# mboard_mcu_2.net
KiCad netlist of a schematic drawn in Altium Designer
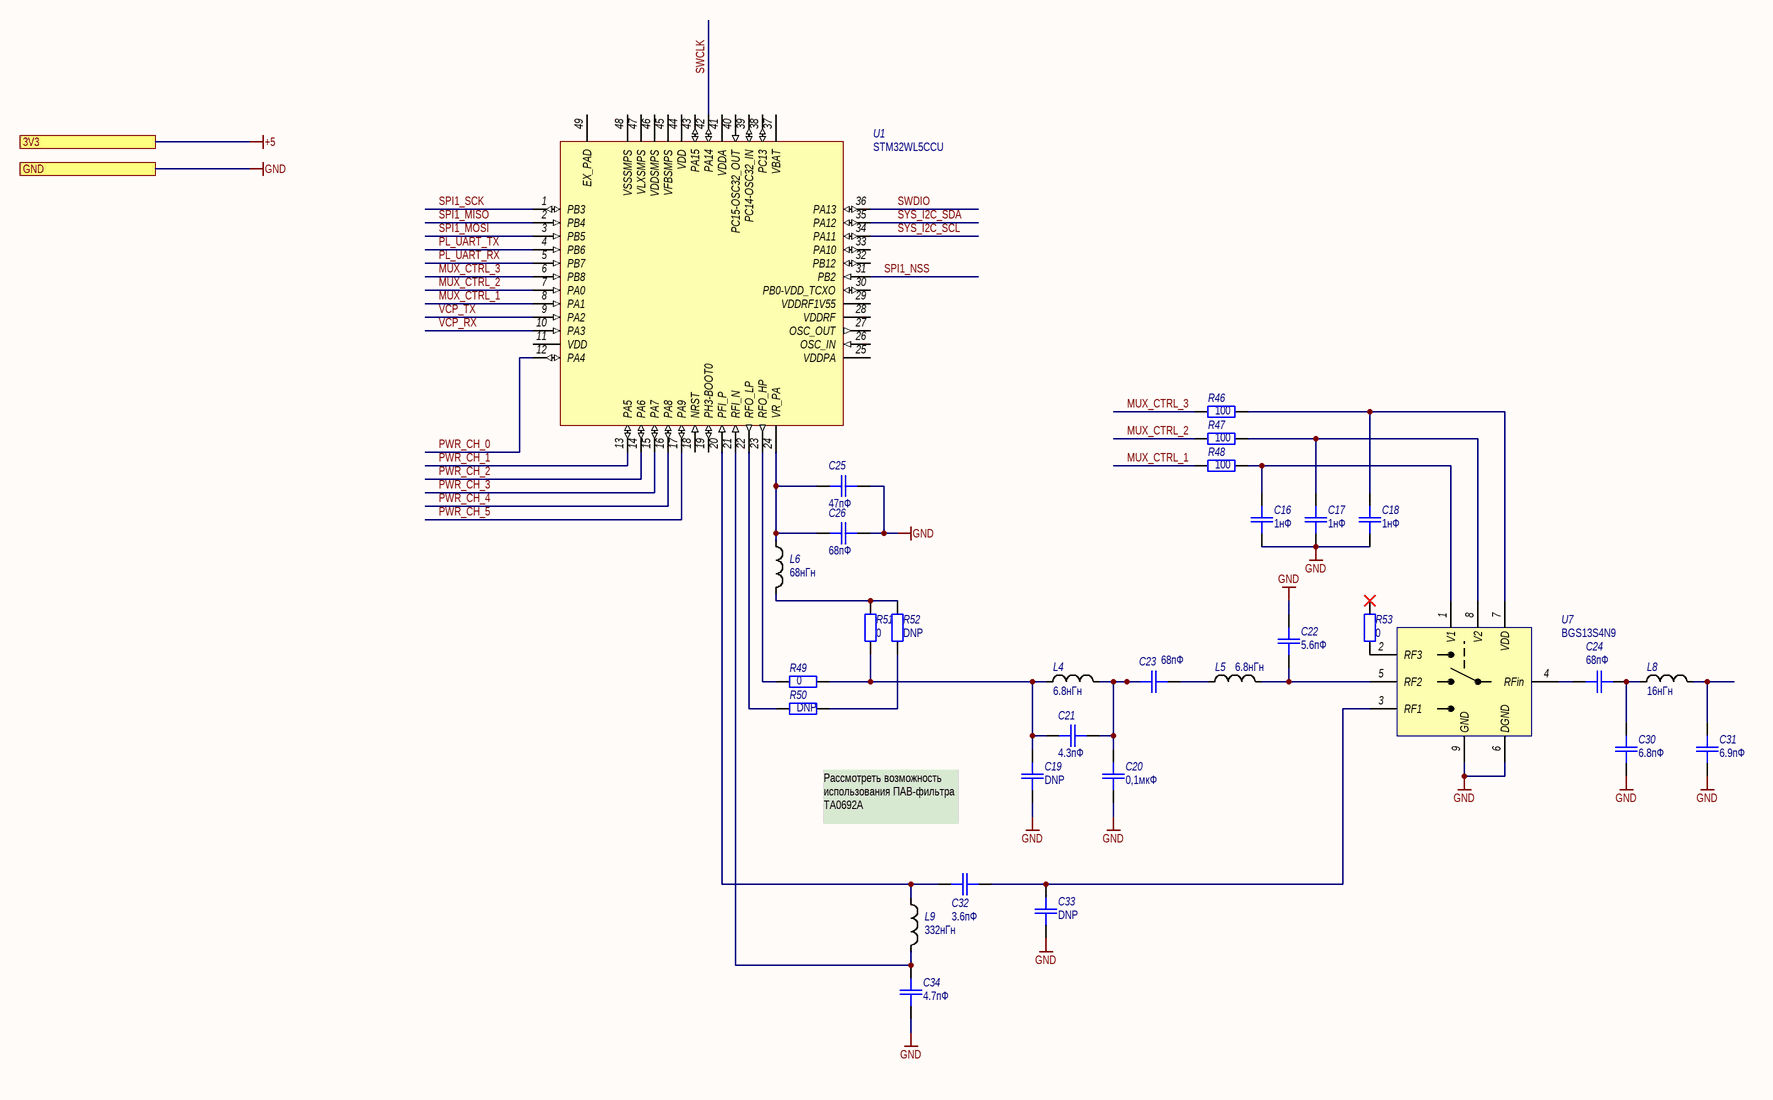
[diagram p0: mboard_mcu (2).SchDoc]

(export (version "E")
  (design (tool "Eeschema 10.0.6"))
  (components
    (comp (ref "C16")
      (value "1нФ")
      (footprint "SMD_C0402")
      (description "Capacitor")
      (fields (field (name "Comment") "K10-79"))
      (libsource (lib "Passive") (part "Capacitor"))
    )
    (comp (ref "C17")
      (value "1нФ")
      (footprint "SMD_C0402")
      (description "Capacitor")
      (fields (field (name "Comment") "K10-79"))
      (libsource (lib "Passive") (part "Capacitor"))
    )
    (comp (ref "C18")
      (value "1нФ")
      (footprint "SMD_C0402")
      (description "Capacitor")
      (fields (field (name "Comment") "K10-79"))
      (libsource (lib "Passive") (part "Capacitor"))
    )
    (comp (ref "C19")
      (value "DNP")
      (footprint "SMD_C0402")
      (description "Capacitor")
      (fields (field (name "Comment") "K10-79"))
      (libsource (lib "Passive") (part "Capacitor"))
    )
    (comp (ref "C20")
      (value "0,1мкФ")
      (footprint "SMD_C0402")
      (description "Capacitor")
      (fields (field (name "Comment") "K10-79"))
      (libsource (lib "Passive") (part "Capacitor"))
    )
    (comp (ref "C21")
      (value "4.3пФ")
      (footprint "SMD_C0402")
      (description "Capacitor")
      (fields (field (name "Comment") "K10-79"))
      (libsource (lib "Passive") (part "Capacitor"))
    )
    (comp (ref "C22")
      (value "5.6пФ")
      (footprint "SMD_C0402")
      (description "Capacitor")
      (fields (field (name "Comment") "K10-79"))
      (libsource (lib "Passive") (part "Capacitor"))
    )
    (comp (ref "C23")
      (value "68пФ")
      (footprint "SMD_C0603")
      (description "Capacitor")
      (fields (field (name "Comment") "K10-79"))
      (libsource (lib "Passive") (part "Capacitor"))
    )
    (comp (ref "C24")
      (value "68пФ")
      (footprint "SMD_C0402")
      (description "Capacitor")
      (fields (field (name "Comment") "K10-79"))
      (libsource (lib "Passive") (part "Capacitor"))
    )
    (comp (ref "C25")
      (value "47пФ")
      (footprint "SMD_C0402")
      (description "Capacitor")
      (fields (field (name "Comment") "K10-79"))
      (libsource (lib "Passive") (part "Capacitor"))
    )
    (comp (ref "C26")
      (value "68пФ")
      (footprint "SMD_C0402")
      (description "Capacitor")
      (fields (field (name "Comment") "K10-79"))
      (libsource (lib "Passive") (part "Capacitor"))
    )
    (comp (ref "C30")
      (value "6.8пФ")
      (footprint "SMD_C0402")
      (description "Capacitor")
      (fields (field (name "Comment") "K10-79"))
      (libsource (lib "Passive") (part "Capacitor"))
    )
    (comp (ref "C31")
      (value "6.9пФ")
      (footprint "SMD_C0402")
      (description "Capacitor")
      (fields (field (name "Comment") "K10-79"))
      (libsource (lib "Passive") (part "Capacitor"))
    )
    (comp (ref "C32")
      (value "3.6пФ")
      (footprint "SMD_C0603")
      (description "Capacitor")
      (fields (field (name "Comment") "K10-79"))
      (libsource (lib "Passive") (part "Capacitor"))
    )
    (comp (ref "C33")
      (value "DNP")
      (footprint "SMD_C0603")
      (description "Capacitor")
      (fields (field (name "Comment") "K10-79"))
      (libsource (lib "Passive") (part "Capacitor"))
    )
    (comp (ref "C34")
      (value "4.7пФ")
      (footprint "SMD_C0603")
      (description "Capacitor")
      (fields (field (name "Comment") "K10-79"))
      (libsource (lib "Passive") (part "Capacitor"))
    )
    (comp (ref "L4")
      (value "6.8нГн")
      (footprint "SMD_0805")
      (description "Inductor")
      (libsource (lib "") (part "Inductor_1"))
    )
    (comp (ref "L5")
      (value "6.8нГн")
      (footprint "SMD_0805")
      (description "Inductor")
      (libsource (lib "Passive") (part "Inductor"))
    )
    (comp (ref "L6")
      (value "68нГн")
      (footprint "SMD_0805")
      (description "Inductor")
      (libsource (lib "Passive") (part "Inductor"))
    )
    (comp (ref "L8")
      (value "16нГн")
      (footprint "SMD_0805")
      (description "Inductor")
      (libsource (lib "Passive") (part "Inductor"))
    )
    (comp (ref "L9")
      (value "332нГн")
      (footprint "SMD_0805")
      (description "Inductor")
      (libsource (lib "Passive") (part "Inductor"))
    )
    (comp (ref "R46")
      (value "100")
      (footprint "SMD_0805")
      (description "Resistor")
      (fields (field (name "Comment") "OSM R1-12"))
      (libsource (lib "") (part "Resistor_1"))
    )
    (comp (ref "R47")
      (value "100")
      (footprint "SMD_0805")
      (description "Resistor")
      (fields (field (name "Comment") "OSM R1-12"))
      (libsource (lib "") (part "Resistor_1"))
    )
    (comp (ref "R48")
      (value "100")
      (footprint "SMD_0805")
      (description "Resistor")
      (fields (field (name "Comment") "OSM R1-12"))
      (libsource (lib "") (part "Resistor_1"))
    )
    (comp (ref "R49")
      (value "0")
      (footprint "SMD_0805")
      (description "Resistor")
      (fields (field (name "Comment") "OSM R1-12"))
      (libsource (lib "") (part "Resistor_1"))
    )
    (comp (ref "R50")
      (value "DNP")
      (footprint "SMD_0805")
      (description "Resistor")
      (fields (field (name "Comment") "OSM R1-12"))
      (libsource (lib "") (part "Resistor_1"))
    )
    (comp (ref "R51")
      (value "0")
      (footprint "SMD_0805")
      (description "Resistor")
      (fields (field (name "Comment") "OSM R1-12"))
      (libsource (lib "") (part "Resistor_2"))
    )
    (comp (ref "R52")
      (value "DNP")
      (footprint "SMD_0805")
      (description "Resistor")
      (fields (field (name "Comment") "OSM R1-12"))
      (libsource (lib "") (part "Resistor_2"))
    )
    (comp (ref "R53")
      (value "0")
      (footprint "SMD_0805")
      (description "Resistor")
      (fields (field (name "Comment") "OSM R1-12"))
      (libsource (lib "Passive") (part "Resistor"))
    )
    (comp (ref "U1")
      (value "STM32WL5CCU")
      (footprint "UQFNPN48")
      (description "Multiprotocol Wireless 32-bit MCU with LPWAN Sub-GHz radio solution")
      (fields (field (name "НАИМЕНОВАНИЕ") "STM32WL5CCU"))
      (libsource (lib "MCU") (part "STM32WL5CCU"))
    )
    (comp (ref "U7")
      (value "BGS13S4N9")
      (footprint "TSNP-9-3")
      (description "Wideband RF SP3T Switch")
      (fields
        (field (name "INTERNAL_PART_NUMBER") "MCD-02018")
        (field (name "MANUFACTURER") "INFINEON")
        (field (name "НАИМЕНОВАНИЕ") "BGS13S4N9")
        (field (name "PROVIDED_BY") "SUBCO")
      )
      (libsource (lib "RF") (part "BGS13S4N9"))
    )
  )
  (nets
    (net (code "2") (name "/MUX_CTRL_1") (class "Default")
      (node (ref "R48") (pin "1") (pinfunction "1_1") (pintype "passive"))
      (node (ref "U1") (pin "8") (pinfunction "PA1_8") (pintype "input"))
    )
    (net (code "3") (name "/MUX_CTRL_2") (class "Default")
      (node (ref "R47") (pin "1") (pinfunction "1_1") (pintype "passive"))
      (node (ref "U1") (pin "7") (pinfunction "PA0_7") (pintype "input"))
    )
    (net (code "4") (name "/MUX_CTRL_3") (class "Default")
      (node (ref "R46") (pin "1") (pinfunction "1_1") (pintype "passive"))
      (node (ref "U1") (pin "6") (pinfunction "PB8_6") (pintype "input"))
    )
    (net (code "5") (name "/PL_UART_RX") (class "Default")
      (node (ref "U1") (pin "5") (pinfunction "PB7_5") (pintype "input"))
    )
    (net (code "6") (name "/PL_UART_TX") (class "Default")
      (node (ref "U1") (pin "4") (pinfunction "PB6_4") (pintype "input"))
    )
    (net (code "7") (name "/PWR_CH_0") (class "Default")
      (node (ref "U1") (pin "12") (pinfunction "PA4_12") (pintype "bidirectional"))
    )
    (net (code "8") (name "/PWR_CH_1") (class "Default")
      (node (ref "U1") (pin "13") (pinfunction "PA5_13") (pintype "bidirectional"))
    )
    (net (code "9") (name "/PWR_CH_2") (class "Default")
      (node (ref "U1") (pin "14") (pinfunction "PA6_14") (pintype "bidirectional"))
    )
    (net (code "10") (name "/PWR_CH_3") (class "Default")
      (node (ref "U1") (pin "15") (pinfunction "PA7_15") (pintype "bidirectional"))
    )
    (net (code "11") (name "/PWR_CH_4") (class "Default")
      (node (ref "U1") (pin "16") (pinfunction "PA8_16") (pintype "bidirectional"))
    )
    (net (code "12") (name "/PWR_CH_5") (class "Default")
      (node (ref "U1") (pin "17") (pinfunction "PA9_17") (pintype "bidirectional"))
    )
    (net (code "13") (name "/SPI1_MISO") (class "Default")
      (node (ref "U1") (pin "2") (pinfunction "PB4_2") (pintype "input"))
    )
    (net (code "14") (name "/SPI1_MOSI") (class "Default")
      (node (ref "U1") (pin "3") (pinfunction "PB5_3") (pintype "input"))
    )
    (net (code "15") (name "/SPI1_NSS") (class "Default")
      (node (ref "U1") (pin "31") (pinfunction "PB2_31") (pintype "input"))
    )
    (net (code "16") (name "/SPI1_SCK") (class "Default")
      (node (ref "U1") (pin "1") (pinfunction "PB3_1") (pintype "bidirectional"))
    )
    (net (code "17") (name "/SWCLK") (class "Default")
      (node (ref "U1") (pin "42") (pinfunction "PA14_42") (pintype "bidirectional"))
    )
    (net (code "18") (name "/SWDIO") (class "Default")
      (node (ref "U1") (pin "36") (pinfunction "PA13_36") (pintype "bidirectional"))
    )
    (net (code "19") (name "/SYS_I2C_SCL") (class "Default")
      (node (ref "U1") (pin "34") (pinfunction "PA11_34") (pintype "bidirectional"))
    )
    (net (code "20") (name "/SYS_I2C_SDA") (class "Default")
      (node (ref "U1") (pin "35") (pinfunction "PA12_35") (pintype "bidirectional"))
    )
    (net (code "21") (name "/VCP_RX") (class "Default")
      (node (ref "U1") (pin "10") (pinfunction "PA3_10") (pintype "input"))
    )
    (net (code "22") (name "/VCP_TX") (class "Default")
      (node (ref "U1") (pin "9") (pinfunction "PA2_9") (pintype "input"))
    )
    (net (code "23") (name "GND") (class "Default")
      (node (ref "C16") (pin "1") (pinfunction "1_1") (pintype "passive"))
      (node (ref "C17") (pin "1") (pinfunction "1_1") (pintype "passive"))
      (node (ref "C18") (pin "1") (pinfunction "1_1") (pintype "passive"))
      (node (ref "C19") (pin "2") (pinfunction "2_2") (pintype "passive"))
      (node (ref "C20") (pin "2") (pinfunction "2_2") (pintype "passive"))
      (node (ref "C22") (pin "2") (pinfunction "2_2") (pintype "passive"))
      (node (ref "C25") (pin "2") (pinfunction "2_2") (pintype "passive"))
      (node (ref "C26") (pin "2") (pinfunction "2_2") (pintype "passive"))
      (node (ref "C30") (pin "1") (pinfunction "1_1") (pintype "passive"))
      (node (ref "C31") (pin "1") (pinfunction "1_1") (pintype "passive"))
      (node (ref "C33") (pin "1") (pinfunction "1_1") (pintype "passive"))
      (node (ref "C34") (pin "2") (pinfunction "2_2") (pintype "passive"))
      (node (ref "U7") (pin "6") (pinfunction "DGND_6") (pintype "passive"))
      (node (ref "U7") (pin "9") (pinfunction "GND_9") (pintype "passive"))
    )
    (net (code "24") (name "Net-(C19-Pad1)") (class "Default")
      (node (ref "C19") (pin "1") (pinfunction "1_1") (pintype "passive"))
      (node (ref "C21") (pin "1") (pinfunction "1_1") (pintype "passive"))
      (node (ref "L4") (pin "2") (pinfunction "2_2") (pintype "passive"))
      (node (ref "R49") (pin "2") (pinfunction "2_2") (pintype "passive"))
      (node (ref "R51") (pin "1") (pinfunction "1_1") (pintype "passive"))
    )
    (net (code "25") (name "Net-(C20-Pad1)") (class "Default")
      (node (ref "C20") (pin "1") (pinfunction "1_1") (pintype "passive"))
      (node (ref "C21") (pin "2") (pinfunction "2_2") (pintype "passive"))
      (node (ref "C23") (pin "1") (pinfunction "1_1") (pintype "passive"))
      (node (ref "L4") (pin "1") (pinfunction "1_1") (pintype "passive"))
    )
    (net (code "26") (name "Net-(C23-Pad2)") (class "Default")
      (node (ref "C23") (pin "2") (pinfunction "2_2") (pintype "passive"))
      (node (ref "L5") (pin "1") (pinfunction "1_1") (pintype "passive"))
    )
    (net (code "27") (name "Net-(C24-Pad2)") (class "Default")
      (node (ref "C24") (pin "2") (pinfunction "2_2") (pintype "passive"))
      (node (ref "C30") (pin "2") (pinfunction "2_2") (pintype "passive"))
      (node (ref "L8") (pin "1") (pinfunction "1_1") (pintype "passive"))
    )
    (net (code "28") (name "Net-(C31-Pad2)") (class "Default")
      (node (ref "C31") (pin "2") (pinfunction "2_2") (pintype "passive"))
      (node (ref "L8") (pin "2") (pinfunction "2_2") (pintype "passive"))
    )
    (net (code "29") (name "Net-(L6-Pad2)") (class "Default")
      (node (ref "L6") (pin "2") (pinfunction "2_2") (pintype "passive"))
      (node (ref "R51") (pin "2") (pinfunction "2_2") (pintype "passive"))
      (node (ref "R52") (pin "2") (pinfunction "2_2") (pintype "passive"))
    )
    (net (code "30") (name "Net-(R50-Pad2)") (class "Default")
      (node (ref "R50") (pin "2") (pinfunction "2_2") (pintype "passive"))
      (node (ref "R52") (pin "1") (pinfunction "1_1") (pintype "passive"))
    )
    (net (code "31") (name "Net-(U1-PFI_P)") (class "Default")
      (node (ref "C32") (pin "1") (pinfunction "1_1") (pintype "passive"))
      (node (ref "L9") (pin "1") (pinfunction "1_1") (pintype "passive"))
      (node (ref "U1") (pin "20") (pinfunction "PFI_P_20") (pintype "input"))
    )
    (net (code "32") (name "Net-(U1-RFI_N)") (class "Default")
      (node (ref "C34") (pin "1") (pinfunction "1_1") (pintype "passive"))
      (node (ref "L9") (pin "2") (pinfunction "2_2") (pintype "passive"))
      (node (ref "U1") (pin "21") (pinfunction "RFI_N_21") (pintype "input"))
    )
    (net (code "33") (name "Net-(U1-RFO_HP)") (class "Default")
      (node (ref "R49") (pin "1") (pinfunction "1_1") (pintype "passive"))
      (node (ref "U1") (pin "23") (pinfunction "RFO_HP_23") (pintype "output"))
    )
    (net (code "34") (name "Net-(U1-RFO_LP)") (class "Default")
      (node (ref "R50") (pin "1") (pinfunction "1_1") (pintype "passive"))
      (node (ref "U1") (pin "22") (pinfunction "RFO_LP_22") (pintype "output"))
    )
    (net (code "35") (name "Net-(U1-VR_PA)") (class "Default")
      (node (ref "C25") (pin "1") (pinfunction "1_1") (pintype "passive"))
      (node (ref "C26") (pin "1") (pinfunction "1_1") (pintype "passive"))
      (node (ref "L6") (pin "1") (pinfunction "1_1") (pintype "passive"))
      (node (ref "U1") (pin "24") (pinfunction "VR_PA_24") (pintype "power_in"))
    )
    (net (code "36") (name "Net-(U7-RF1)") (class "Default")
      (node (ref "C32") (pin "2") (pinfunction "2_2") (pintype "passive"))
      (node (ref "C33") (pin "2") (pinfunction "2_2") (pintype "passive"))
      (node (ref "U7") (pin "3") (pinfunction "RF1_3") (pintype "passive"))
    )
    (net (code "37") (name "Net-(U7-RF2)") (class "Default")
      (node (ref "C22") (pin "1") (pinfunction "1_1") (pintype "passive"))
      (node (ref "L5") (pin "2") (pinfunction "2_2") (pintype "passive"))
      (node (ref "U7") (pin "5") (pinfunction "RF2_5") (pintype "passive"))
    )
    (net (code "38") (name "Net-(U7-RF3)") (class "Default")
      (node (ref "R53") (pin "2") (pinfunction "2_2") (pintype "passive"))
      (node (ref "U7") (pin "2") (pinfunction "RF3_2") (pintype "passive"))
    )
    (net (code "39") (name "Net-(U7-RFin)") (class "Default")
      (node (ref "C24") (pin "1") (pinfunction "1_1") (pintype "passive"))
      (node (ref "U7") (pin "4") (pinfunction "RFin_4") (pintype "passive"))
    )
    (net (code "40") (name "Net-(U7-V1)") (class "Default")
      (node (ref "C16") (pin "2") (pinfunction "2_2") (pintype "passive"))
      (node (ref "R48") (pin "2") (pinfunction "2_2") (pintype "passive"))
      (node (ref "U7") (pin "1") (pinfunction "V1_1") (pintype "passive"))
    )
    (net (code "41") (name "Net-(U7-V2)") (class "Default")
      (node (ref "C17") (pin "2") (pinfunction "2_2") (pintype "passive"))
      (node (ref "R47") (pin "2") (pinfunction "2_2") (pintype "passive"))
      (node (ref "U7") (pin "8") (pinfunction "V2_8") (pintype "passive"))
    )
    (net (code "42") (name "Net-(U7-VDD)") (class "Default")
      (node (ref "C18") (pin "2") (pinfunction "2_2") (pintype "passive"))
      (node (ref "R46") (pin "2") (pinfunction "2_2") (pintype "passive"))
      (node (ref "U7") (pin "7") (pinfunction "VDD_7") (pintype "passive"))
    )
    (net (code "43") (name "unconnected-(R53-Pad1)") (class "Default")
      (node (ref "R53") (pin "1") (pinfunction "1_1") (pintype "passive+no_connect"))
    )
    (net (code "44") (name "unconnected-(U1-EX_PAD-Pad49)") (class "Default")
      (node (ref "U1") (pin "49") (pinfunction "EX_PAD_49") (pintype "power_in"))
    )
    (net (code "45") (name "unconnected-(U1-NRST-Pad18)") (class "Default")
      (node (ref "U1") (pin "18") (pinfunction "NRST_18") (pintype "input"))
    )
    (net (code "46") (name "unconnected-(U1-OSC_IN-Pad26)") (class "Default")
      (node (ref "U1") (pin "26") (pinfunction "OSC_IN_26") (pintype "input"))
    )
    (net (code "47") (name "unconnected-(U1-OSC_OUT-Pad27)") (class "Default")
      (node (ref "U1") (pin "27") (pinfunction "OSC_OUT_27") (pintype "output"))
    )
    (net (code "48") (name "unconnected-(U1-PA10-Pad33)") (class "Default")
      (node (ref "U1") (pin "33") (pinfunction "PA10_33") (pintype "bidirectional"))
    )
    (net (code "49") (name "unconnected-(U1-PA15-Pad43)") (class "Default")
      (node (ref "U1") (pin "43") (pinfunction "PA15_43") (pintype "bidirectional"))
    )
    (net (code "50") (name "unconnected-(U1-PB0-VDD_TCXO-Pad30)") (class "Default")
      (node (ref "U1") (pin "30") (pinfunction "PB0-VDD_TCXO_30") (pintype "bidirectional"))
    )
    (net (code "51") (name "unconnected-(U1-PB12-Pad32)") (class "Default")
      (node (ref "U1") (pin "32") (pinfunction "PB12_32") (pintype "bidirectional"))
    )
    (net (code "52") (name "unconnected-(U1-PC13-Pad38)") (class "Default")
      (node (ref "U1") (pin "38") (pinfunction "PC13_38") (pintype "bidirectional"))
    )
    (net (code "53") (name "unconnected-(U1-PC14-OSC32_IN-Pad39)") (class "Default")
      (node (ref "U1") (pin "39") (pinfunction "PC14-OSC32_IN_39") (pintype "bidirectional"))
    )
    (net (code "54") (name "unconnected-(U1-PC15-OSC32_OUT-Pad40)") (class "Default")
      (node (ref "U1") (pin "40") (pinfunction "PC15-OSC32_OUT_40") (pintype "input"))
    )
    (net (code "55") (name "unconnected-(U1-PH3-BOOT0-Pad19)") (class "Default")
      (node (ref "U1") (pin "19") (pinfunction "PH3-BOOT0_19") (pintype "bidirectional"))
    )
    (net (code "56") (name "unconnected-(U1-VBAT-Pad37)") (class "Default")
      (node (ref "U1") (pin "37") (pinfunction "VBAT_37") (pintype "power_in"))
    )
    (net (code "57") (name "unconnected-(U1-VDD-Pad11)") (class "Default")
      (node (ref "U1") (pin "11") (pinfunction "VDD_11") (pintype "power_in"))
    )
    (net (code "58") (name "unconnected-(U1-VDD-Pad44)") (class "Default")
      (node (ref "U1") (pin "44") (pinfunction "VDD_44") (pintype "power_in"))
    )
    (net (code "59") (name "unconnected-(U1-VDDA-Pad41)") (class "Default")
      (node (ref "U1") (pin "41") (pinfunction "VDDA_41") (pintype "power_in"))
    )
    (net (code "60") (name "unconnected-(U1-VDDPA-Pad25)") (class "Default")
      (node (ref "U1") (pin "25") (pinfunction "VDDPA_25") (pintype "power_in"))
    )
    (net (code "61") (name "unconnected-(U1-VDDRF-Pad28)") (class "Default")
      (node (ref "U1") (pin "28") (pinfunction "VDDRF_28") (pintype "power_in"))
    )
    (net (code "62") (name "unconnected-(U1-VDDRF1V55-Pad29)") (class "Default")
      (node (ref "U1") (pin "29") (pinfunction "VDDRF1V55_29") (pintype "power_in"))
    )
    (net (code "63") (name "unconnected-(U1-VDDSMPS-Pad46)") (class "Default")
      (node (ref "U1") (pin "46") (pinfunction "VDDSMPS_46") (pintype "power_in"))
    )
    (net (code "64") (name "unconnected-(U1-VFBSMPS-Pad45)") (class "Default")
      (node (ref "U1") (pin "45") (pinfunction "VFBSMPS_45") (pintype "power_in"))
    )
    (net (code "65") (name "unconnected-(U1-VLXSMPS-Pad47)") (class "Default")
      (node (ref "U1") (pin "47") (pinfunction "VLXSMPS_47") (pintype "power_in"))
    )
    (net (code "66") (name "unconnected-(U1-VSSSMPS-Pad48)") (class "Default")
      (node (ref "U1") (pin "48") (pinfunction "VSSSMPS_48") (pintype "power_in"))
    )
  )
)
